# Polarshield_v2_2.net
KiCad netlist of a schematic drawn in EAGLE
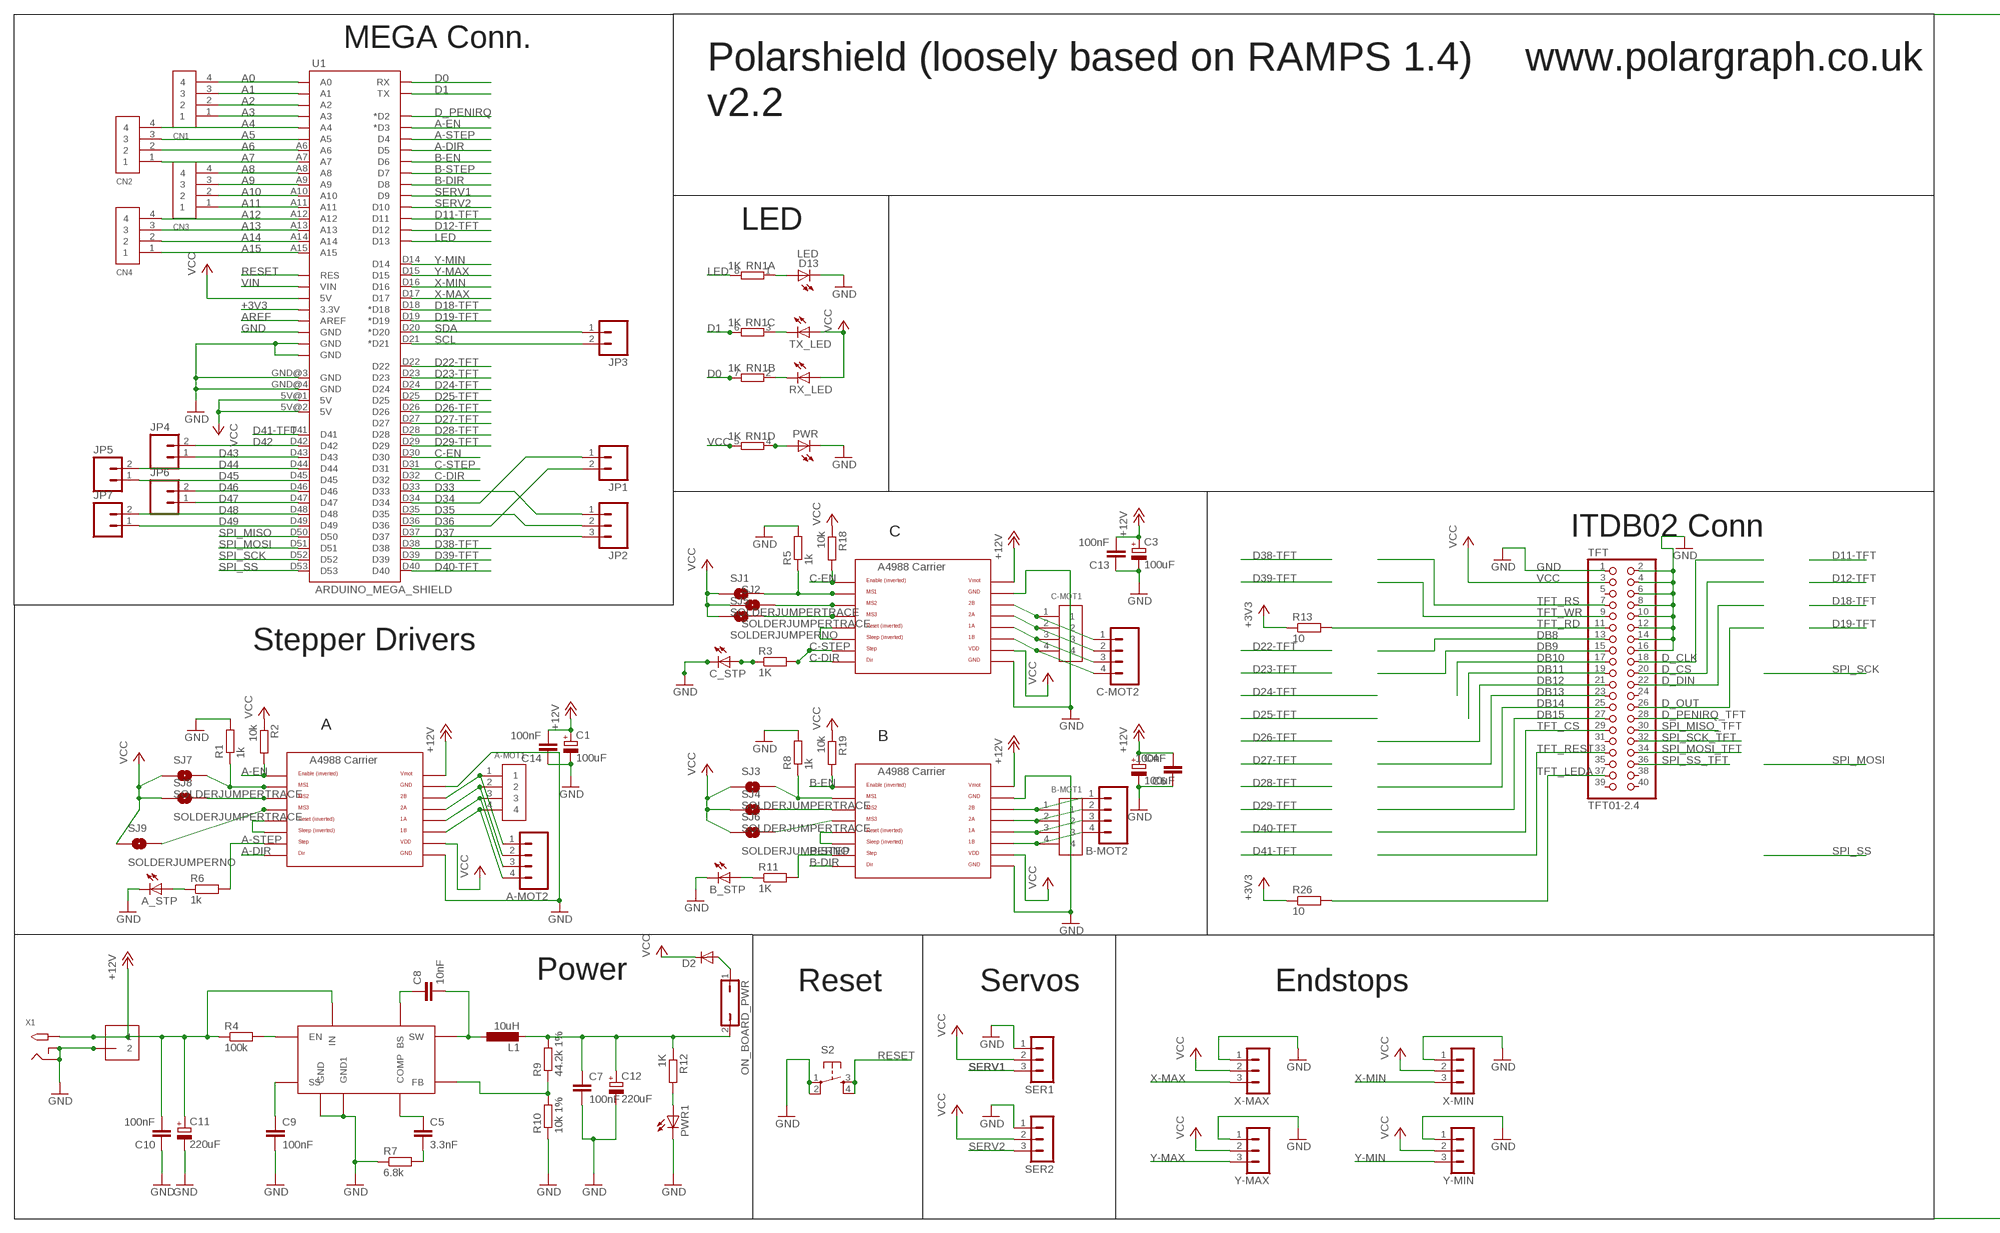
[diagram p0: schematic, sheet 1, part 1 of 2]
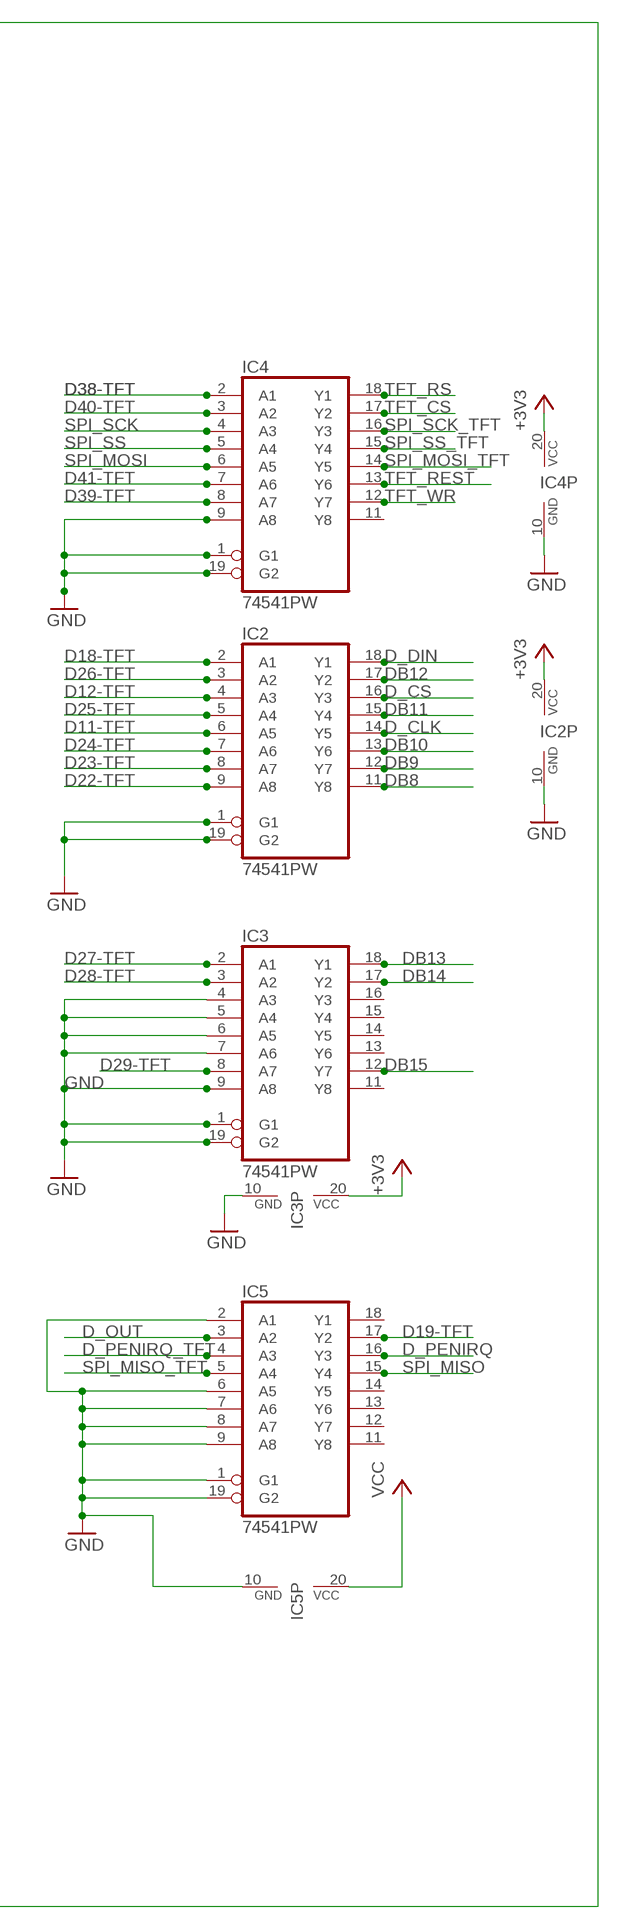
[diagram p1: schematic, sheet 1, part 2 of 2]

(export (version "E")
  (design (tool "Eeschema 10.0.6"))
  (components
    (comp (ref "A-MOT1")
      (value "1X4-BIG")
      (footprint "eagle-import:1X04-BIG")
      (libsource (lib "eagle-import") (part "adafruit_1X4-BIG"))
    )
    (comp (ref "A-MOT2")
      (value "M04SCREW")
      (footprint "eagle-import:SCREWTERMINAL-3.5MM-4")
      (libsource (lib "eagle-import") (part "M04SCREW"))
    )
    (comp (ref "A_STP")
      (value "LEDCHIP-LED0805")
      (footprint "eagle-import:CHIP-LED0805")
      (libsource (lib "eagle-import") (part "LEDCHIP-LED0805"))
    )
    (comp (ref "B-MOT1")
      (value "1X4-BIG")
      (footprint "eagle-import:1X04-BIG")
      (libsource (lib "eagle-import") (part "adafruit_1X4-BIG"))
    )
    (comp (ref "B-MOT2")
      (value "M04SCREW")
      (footprint "eagle-import:SCREWTERMINAL-3.5MM-4")
      (libsource (lib "eagle-import") (part "M04SCREW"))
    )
    (comp (ref "B_STP")
      (value "LEDCHIP-LED0805")
      (footprint "eagle-import:CHIP-LED0805")
      (libsource (lib "eagle-import") (part "LEDCHIP-LED0805"))
    )
    (comp (ref "C-MOT1")
      (value "1X4-BIG")
      (footprint "eagle-import:1X04-BIG")
      (libsource (lib "eagle-import") (part "adafruit_1X4-BIG"))
    )
    (comp (ref "C-MOT2")
      (value "M04SCREW")
      (footprint "eagle-import:SCREWTERMINAL-3.5MM-4")
      (libsource (lib "eagle-import") (part "M04SCREW"))
    )
    (comp (ref "C1")
      (value "100uF")
      (footprint "eagle-import:153CLV-0605")
      (libsource (lib "eagle-import") (part "CPOL-EU153CLV-0605"))
    )
    (comp (ref "C3")
      (value "100uF")
      (footprint "eagle-import:153CLV-0605")
      (libsource (lib "eagle-import") (part "CPOL-EU153CLV-0605"))
    )
    (comp (ref "C4")
      (value "100uF")
      (footprint "eagle-import:153CLV-0605")
      (libsource (lib "eagle-import") (part "CPOL-EU153CLV-0605"))
    )
    (comp (ref "C5")
      (value "3.3nF")
      (footprint "eagle-import:C0805K")
      (libsource (lib "eagle-import") (part "C-EUC0805K"))
    )
    (comp (ref "C6")
      (value "100nF")
      (footprint "eagle-import:C0805")
      (libsource (lib "eagle-import") (part "C-EUC0805"))
    )
    (comp (ref "C7")
      (value "100nF")
      (footprint "eagle-import:C0805K")
      (libsource (lib "eagle-import") (part "C-EUC0805K"))
    )
    (comp (ref "C8")
      (value "10nF")
      (footprint "eagle-import:C0805K")
      (libsource (lib "eagle-import") (part "C-EUC0805K"))
    )
    (comp (ref "C9")
      (value "100nF")
      (footprint "eagle-import:C0805K")
      (libsource (lib "eagle-import") (part "C-EUC0805K"))
    )
    (comp (ref "C10")
      (value "100nF")
      (footprint "eagle-import:C0805K")
      (libsource (lib "eagle-import") (part "C-EUC0805K"))
    )
    (comp (ref "C11")
      (value "220uF")
      (footprint "eagle-import:153CLV-0807")
      (libsource (lib "eagle-import") (part "resistor_CPOL-EU153CLV-0807"))
    )
    (comp (ref "C12")
      (value "220uF")
      (footprint "eagle-import:153CLV-0807")
      (libsource (lib "eagle-import") (part "resistor_CPOL-EU153CLV-0807"))
    )
    (comp (ref "C13")
      (value "100nF")
      (footprint "eagle-import:C0805")
      (libsource (lib "eagle-import") (part "C-EUC0805"))
    )
    (comp (ref "C14")
      (value "100nF")
      (footprint "eagle-import:C0805")
      (libsource (lib "eagle-import") (part "C-EUC0805"))
    )
    (comp (ref "CN1")
      (value "1X4-CLEANBIG")
      (footprint "eagle-import:1X04-CLEANBIG")
      (libsource (lib "eagle-import") (part "1X4-CLEANBIG"))
    )
    (comp (ref "CN2")
      (value "1X4-CLEANBIG")
      (footprint "eagle-import:1X04-CLEANBIG")
      (libsource (lib "eagle-import") (part "1X4-CLEANBIG"))
    )
    (comp (ref "CN3")
      (value "1X4-CLEANBIG")
      (footprint "eagle-import:1X04-CLEANBIG")
      (libsource (lib "eagle-import") (part "1X4-CLEANBIG"))
    )
    (comp (ref "CN4")
      (value "1X4-CLEANBIG")
      (footprint "eagle-import:1X04-CLEANBIG")
      (libsource (lib "eagle-import") (part "1X4-CLEANBIG"))
    )
    (comp (ref "C_STP")
      (value "LEDCHIP-LED0805")
      (footprint "eagle-import:CHIP-LED0805")
      (libsource (lib "eagle-import") (part "LEDCHIP-LED0805"))
    )
    (comp (ref "D2")
      (value "DIODE-DO214BA")
      (footprint "eagle-import:DO214BA")
      (libsource (lib "eagle-import") (part "DIODE-DO214BA"))
    )
    (comp (ref "D13")
      (value "LED")
      (footprint "eagle-import:CHIP-LED0805")
      (libsource (lib "eagle-import") (part "LEDCHIP-LED0805"))
    )
    (comp (ref "IC1")
      (value "MP2307")
      (footprint "eagle-import:SOIC8")
      (libsource (lib "eagle-import") (part "MP2307"))
    )
    (comp (ref "IC2")
      (value "74541PW")
      (footprint "eagle-import:TSSOP20")
      (libsource (lib "eagle-import") (part "74541PW"))
    )
    (comp (ref "IC3")
      (value "74541PW")
      (footprint "eagle-import:TSSOP20")
      (libsource (lib "eagle-import") (part "74541PW"))
    )
    (comp (ref "IC4")
      (value "74541PW")
      (footprint "eagle-import:TSSOP20")
      (libsource (lib "eagle-import") (part "74541PW"))
    )
    (comp (ref "IC5")
      (value "74541PW")
      (footprint "eagle-import:TSSOP20")
      (libsource (lib "eagle-import") (part "74541PW"))
    )
    (comp (ref "J1")
      (value "1X2-3.5MM")
      (footprint "eagle-import:1X2-3.5MM")
      (libsource (lib "eagle-import") (part "1X2-3.5MM"))
    )
    (comp (ref "JP1")
      (value "M02POGO_PIN_HOLES_ONLY")
      (footprint "eagle-import:1X02_PP_HOLES_ONLY")
      (libsource (lib "eagle-import") (part "M02POGO_PIN_HOLES_ONLY"))
    )
    (comp (ref "JP2")
      (value "M03POGO_PIN_HOLES_ONLY")
      (footprint "eagle-import:1X03_PP_HOLES_ONLY")
      (libsource (lib "eagle-import") (part "M03POGO_PIN_HOLES_ONLY"))
    )
    (comp (ref "JP3")
      (value "M02POGO_PIN_HOLES_ONLY")
      (footprint "eagle-import:1X02_PP_HOLES_ONLY")
      (libsource (lib "eagle-import") (part "M02POGO_PIN_HOLES_ONLY"))
    )
    (comp (ref "JP4")
      (value "M02POGO_PIN_HOLES_ONLY")
      (footprint "eagle-import:1X02_PP_HOLES_ONLY")
      (libsource (lib "eagle-import") (part "M02POGO_PIN_HOLES_ONLY"))
    )
    (comp (ref "JP5")
      (value "M02POGO_PIN_HOLES_ONLY")
      (footprint "eagle-import:1X02_PP_HOLES_ONLY")
      (libsource (lib "eagle-import") (part "M02POGO_PIN_HOLES_ONLY"))
    )
    (comp (ref "JP6")
      (value "M02POGO_PIN_HOLES_ONLY")
      (footprint "eagle-import:1X02_PP_HOLES_ONLY")
      (libsource (lib "eagle-import") (part "M02POGO_PIN_HOLES_ONLY"))
    )
    (comp (ref "JP7")
      (value "M02POGO_PIN_HOLES_ONLY")
      (footprint "eagle-import:1X02_PP_HOLES_ONLY")
      (libsource (lib "eagle-import") (part "M02POGO_PIN_HOLES_ONLY"))
    )
    (comp (ref "L1")
      (value "10uH")
      (footprint "eagle-import:PIS2816")
      (libsource (lib "eagle-import") (part "L-EUPIS2816"))
    )
    (comp (ref "ON_BOARD_PWR")
      (value "JP1Q")
      (footprint "eagle-import:JP1")
      (libsource (lib "eagle-import") (part "JP1Q"))
    )
    (comp (ref "PWR")
      (value "LEDCHIP-LED0805")
      (footprint "eagle-import:CHIP-LED0805")
      (libsource (lib "eagle-import") (part "LEDCHIP-LED0805"))
    )
    (comp (ref "PWR1")
      (value "LEDCHIP-LED0805")
      (footprint "eagle-import:CHIP-LED0805")
      (libsource (lib "eagle-import") (part "LEDCHIP-LED0805"))
    )
    (comp (ref "R1")
      (value "1k")
      (footprint "eagle-import:R0805")
      (libsource (lib "eagle-import") (part "R-EU_R0805"))
    )
    (comp (ref "R2")
      (value "10k")
      (footprint "eagle-import:R0805")
      (libsource (lib "eagle-import") (part "R-EU_R0805"))
    )
    (comp (ref "R3")
      (value "1K")
      (footprint "eagle-import:R0805")
      (libsource (lib "eagle-import") (part "R-EU_R0805"))
    )
    (comp (ref "R4")
      (value "100k")
      (footprint "eagle-import:R0805")
      (libsource (lib "eagle-import") (part "resistor_R-EU_R0805"))
    )
    (comp (ref "R5")
      (value "1k")
      (footprint "eagle-import:R0805")
      (libsource (lib "eagle-import") (part "R-EU_R0805"))
    )
    (comp (ref "R6")
      (value "1k")
      (footprint "eagle-import:R0805")
      (libsource (lib "eagle-import") (part "R-EU_R0805"))
    )
    (comp (ref "R7")
      (value "6.8k")
      (footprint "eagle-import:R0805")
      (libsource (lib "eagle-import") (part "resistor_R-EU_R0805"))
    )
    (comp (ref "R8")
      (value "1k")
      (footprint "eagle-import:R0805")
      (libsource (lib "eagle-import") (part "R-EU_R0805"))
    )
    (comp (ref "R9")
      (value "44.2k 1%")
      (footprint "eagle-import:R0805")
      (libsource (lib "eagle-import") (part "resistor_R-EU_R0805"))
    )
    (comp (ref "R10")
      (value "10k 1%")
      (footprint "eagle-import:R0805")
      (libsource (lib "eagle-import") (part "resistor_R-EU_R0805"))
    )
    (comp (ref "R11")
      (value "1K")
      (footprint "eagle-import:R0805")
      (libsource (lib "eagle-import") (part "R-EU_R0805"))
    )
    (comp (ref "R12")
      (value "1K")
      (footprint "eagle-import:R0805")
      (libsource (lib "eagle-import") (part "R-EU_R0805"))
    )
    (comp (ref "R13")
      (value "10")
      (footprint "eagle-import:R0805")
      (libsource (lib "eagle-import") (part "resistor_R-EU_R0805"))
    )
    (comp (ref "R18")
      (value "10k")
      (footprint "eagle-import:R0805")
      (libsource (lib "eagle-import") (part "R-EU_R0805"))
    )
    (comp (ref "R19")
      (value "10k")
      (footprint "eagle-import:R0805")
      (libsource (lib "eagle-import") (part "R-EU_R0805"))
    )
    (comp (ref "R26")
      (value "10")
      (footprint "eagle-import:R0805")
      (libsource (lib "eagle-import") (part "resistor_R-EU_R0805"))
    )
    (comp (ref "RN1")
      (value "1K")
      (footprint "eagle-import:EXBS8V")
      (libsource (lib "eagle-import") (part "4R-NEXBS8V"))
    )
    (comp (ref "RX_LED")
      (value "LEDCHIP-LED0805")
      (footprint "eagle-import:CHIP-LED0805")
      (libsource (lib "eagle-import") (part "LEDCHIP-LED0805"))
    )
    (comp (ref "S2")
      (value "TAC_SWITCHPTH")
      (footprint "eagle-import:TACTILE-PTH")
      (libsource (lib "eagle-import") (part "TAC_SWITCHPTH"))
    )
    (comp (ref "SER1")
      (value "3PIN-HEADER")
      (footprint "eagle-import:3PIN-HEADER")
      (libsource (lib "eagle-import") (part "3PIN-HEADER"))
    )
    (comp (ref "SER2")
      (value "3PIN-HEADER")
      (footprint "eagle-import:3PIN-HEADER")
      (libsource (lib "eagle-import") (part "3PIN-HEADER"))
    )
    (comp (ref "SJ1")
      (value "SOLDERJUMPERTRACE")
      (footprint "eagle-import:SJ_2S-TRACE")
      (libsource (lib "eagle-import") (part "SOLDERJUMPERTRACE"))
    )
    (comp (ref "SJ2")
      (value "SOLDERJUMPERTRACE")
      (footprint "eagle-import:SJ_2S-TRACE")
      (libsource (lib "eagle-import") (part "SOLDERJUMPERTRACE"))
    )
    (comp (ref "SJ3")
      (value "SOLDERJUMPERTRACE")
      (footprint "eagle-import:SJ_2S-TRACE")
      (libsource (lib "eagle-import") (part "SOLDERJUMPERTRACE"))
    )
    (comp (ref "SJ4")
      (value "SOLDERJUMPERTRACE")
      (footprint "eagle-import:SJ_2S-TRACE")
      (libsource (lib "eagle-import") (part "SOLDERJUMPERTRACE"))
    )
    (comp (ref "SJ5")
      (value "SOLDERJUMPERNO")
      (footprint "eagle-import:SJ_2S-NO")
      (libsource (lib "eagle-import") (part "SOLDERJUMPERNO"))
    )
    (comp (ref "SJ6")
      (value "SOLDERJUMPERNO")
      (footprint "eagle-import:SJ_2S-NO")
      (libsource (lib "eagle-import") (part "SOLDERJUMPERNO"))
    )
    (comp (ref "SJ7")
      (value "SOLDERJUMPERTRACE")
      (footprint "eagle-import:SJ_2S-TRACE")
      (libsource (lib "eagle-import") (part "SOLDERJUMPERTRACE"))
    )
    (comp (ref "SJ8")
      (value "SOLDERJUMPERTRACE")
      (footprint "eagle-import:SJ_2S-TRACE")
      (libsource (lib "eagle-import") (part "SOLDERJUMPERTRACE"))
    )
    (comp (ref "SJ9")
      (value "SOLDERJUMPERNO")
      (footprint "eagle-import:SJ_2S-NO")
      (libsource (lib "eagle-import") (part "SOLDERJUMPERNO"))
    )
    (comp (ref "TFT")
      (value "TFT01-2.4")
      (footprint "eagle-import:TFT01-2.4")
      (libsource (lib "eagle-import") (part "TFT01-2.4"))
    )
    (comp (ref "TX_LED")
      (value "LEDCHIP-LED0805")
      (footprint "eagle-import:CHIP-LED0805")
      (libsource (lib "eagle-import") (part "LEDCHIP-LED0805"))
    )
    (comp (ref "U$1")
      (value "A4988BREAKOUT")
      (footprint "eagle-import:A4988BREAKOUT")
      (libsource (lib "eagle-import") (part "A4988BREAKOUT"))
    )
    (comp (ref "U$6")
      (value "A4988BREAKOUT")
      (footprint "eagle-import:A4988BREAKOUT")
      (libsource (lib "eagle-import") (part "A4988BREAKOUT"))
    )
    (comp (ref "U$7")
      (value "A4988BREAKOUT")
      (footprint "eagle-import:A4988BREAKOUT")
      (libsource (lib "eagle-import") (part "A4988BREAKOUT"))
    )
    (comp (ref "U1")
      (value "ARDUINO_MEGA_SHIELD")
      (footprint "eagle-import:ARDUINO_MEGA_SHIELD")
      (libsource (lib "eagle-import") (part "ARDUINO_MEGA_SHIELD"))
    )
    (comp (ref "X-MAX")
      (value "3PIN-HEADER")
      (footprint "eagle-import:3PIN-HEADER")
      (libsource (lib "eagle-import") (part "3PIN-HEADER"))
    )
    (comp (ref "X-MIN")
      (value "3PIN-HEADER")
      (footprint "eagle-import:3PIN-HEADER")
      (libsource (lib "eagle-import") (part "3PIN-HEADER"))
    )
    (comp (ref "X1")
      (value "2.1MMJACKTHM")
      (footprint "eagle-import:PJ-102A")
      (libsource (lib "eagle-import") (part "2.1MMJACKTHM"))
    )
    (comp (ref "Y-MAX")
      (value "3PIN-HEADER")
      (footprint "eagle-import:3PIN-HEADER")
      (libsource (lib "eagle-import") (part "3PIN-HEADER"))
    )
    (comp (ref "Y-MIN")
      (value "3PIN-HEADER")
      (footprint "eagle-import:3PIN-HEADER")
      (libsource (lib "eagle-import") (part "3PIN-HEADER"))
    )
  )
  (nets
    (net (code "1") (name "+3V3") (class "Default")
      (node (ref "IC2") (pin "20") (pinfunction "VCC_20") (pintype "power_in"))
      (node (ref "IC3") (pin "20") (pinfunction "VCC_20") (pintype "power_in"))
      (node (ref "IC4") (pin "20") (pinfunction "VCC_20") (pintype "power_in"))
      (node (ref "R13") (pin "1") (pinfunction "1_1") (pintype "passive"))
      (node (ref "R26") (pin "1") (pinfunction "1_1") (pintype "passive"))
      (node (ref "U1") (pin "3.3V") (pinfunction "3.3V_3.3V") (pintype "bidirectional"))
    )
    (net (code "2") (name "+12V") (class "Default")
      (node (ref "C1") (pin "+") (pinfunction "+_+") (pintype "passive"))
      (node (ref "C10") (pin "2") (pinfunction "2_2") (pintype "passive"))
      (node (ref "C11") (pin "+") (pinfunction "+_+") (pintype "passive"))
      (node (ref "C13") (pin "2") (pinfunction "2_2") (pintype "passive"))
      (node (ref "C14") (pin "2") (pinfunction "2_2") (pintype "passive"))
      (node (ref "C3") (pin "+") (pinfunction "+_+") (pintype "passive"))
      (node (ref "C4") (pin "+") (pinfunction "+_+") (pintype "passive"))
      (node (ref "C6") (pin "2") (pinfunction "2_2") (pintype "passive"))
      (node (ref "IC1") (pin "IN") (pinfunction "IN_IN") (pintype "bidirectional"))
      (node (ref "J1") (pin "1") (pinfunction "1_1") (pintype "passive"))
      (node (ref "R4") (pin "1") (pinfunction "1_1") (pintype "passive"))
      (node (ref "U$1") (pin "VMOT") (pinfunction "VMOT_VMOT") (pintype "power_in"))
      (node (ref "U$6") (pin "VMOT") (pinfunction "VMOT_VMOT") (pintype "power_in"))
      (node (ref "U$7") (pin "VMOT") (pinfunction "VMOT_VMOT") (pintype "power_in"))
      (node (ref "X1") (pin "TIP") (pinfunction "TIP_TIP") (pintype "bidirectional"))
    )
    (net (code "3") (name "/A-DIR") (class "Default")
      (node (ref "U$1") (pin "DIR") (pinfunction "DIR_DIR") (pintype "input"))
      (node (ref "U1") (pin "D5") (pinfunction "D5_D5") (pintype "bidirectional"))
    )
    (net (code "4") (name "/A-EN") (class "Default")
      (node (ref "R2") (pin "2") (pinfunction "2_2") (pintype "passive"))
      (node (ref "U$1") (pin "EN") (pinfunction "EN_EN") (pintype "input"))
      (node (ref "U1") (pin "D3") (pinfunction "*D3_D3") (pintype "bidirectional"))
    )
    (net (code "5") (name "/A-STEP") (class "Default")
      (node (ref "R6") (pin "2") (pinfunction "2_2") (pintype "passive"))
      (node (ref "U$1") (pin "STEP") (pinfunction "STEP_STEP") (pintype "input"))
      (node (ref "U1") (pin "D4") (pinfunction "D4_D4") (pintype "bidirectional"))
    )
    (net (code "6") (name "/A0") (class "Default")
      (node (ref "CN1") (pin "4") (pinfunction "4_4") (pintype "bidirectional"))
      (node (ref "U1") (pin "A0") (pinfunction "A0_A0") (pintype "bidirectional"))
    )
    (net (code "7") (name "/A1") (class "Default")
      (node (ref "CN1") (pin "3") (pinfunction "3_3") (pintype "bidirectional"))
      (node (ref "U1") (pin "A1") (pinfunction "A1_A1") (pintype "bidirectional"))
    )
    (net (code "8") (name "/A2") (class "Default")
      (node (ref "CN1") (pin "2") (pinfunction "2_2") (pintype "bidirectional"))
      (node (ref "U1") (pin "A2") (pinfunction "A2_A2") (pintype "bidirectional"))
    )
    (net (code "9") (name "/A3") (class "Default")
      (node (ref "CN1") (pin "1") (pinfunction "1_1") (pintype "bidirectional"))
      (node (ref "U1") (pin "A3") (pinfunction "A3_A3") (pintype "bidirectional"))
    )
    (net (code "10") (name "/A4") (class "Default")
      (node (ref "CN2") (pin "4") (pinfunction "4_4") (pintype "bidirectional"))
      (node (ref "U1") (pin "A4") (pinfunction "A4_A4") (pintype "bidirectional"))
    )
    (net (code "11") (name "/A5") (class "Default")
      (node (ref "CN2") (pin "3") (pinfunction "3_3") (pintype "bidirectional"))
      (node (ref "U1") (pin "A5") (pinfunction "A5_A5") (pintype "bidirectional"))
    )
    (net (code "12") (name "/A6") (class "Default")
      (node (ref "CN2") (pin "2") (pinfunction "2_2") (pintype "bidirectional"))
      (node (ref "U1") (pin "A6") (pinfunction "A6_A6") (pintype "bidirectional"))
    )
    (net (code "13") (name "/A7") (class "Default")
      (node (ref "CN2") (pin "1") (pinfunction "1_1") (pintype "bidirectional"))
      (node (ref "U1") (pin "A7") (pinfunction "A7_A7") (pintype "bidirectional"))
    )
    (net (code "14") (name "/A8") (class "Default")
      (node (ref "CN3") (pin "4") (pinfunction "4_4") (pintype "bidirectional"))
      (node (ref "U1") (pin "A8") (pinfunction "A8_A8") (pintype "bidirectional"))
    )
    (net (code "15") (name "/A9") (class "Default")
      (node (ref "CN3") (pin "3") (pinfunction "3_3") (pintype "bidirectional"))
      (node (ref "U1") (pin "A9") (pinfunction "A9_A9") (pintype "bidirectional"))
    )
    (net (code "16") (name "/A10") (class "Default")
      (node (ref "CN3") (pin "2") (pinfunction "2_2") (pintype "bidirectional"))
      (node (ref "U1") (pin "A10") (pinfunction "A10_A10") (pintype "bidirectional"))
    )
    (net (code "17") (name "/A11") (class "Default")
      (node (ref "CN3") (pin "1") (pinfunction "1_1") (pintype "bidirectional"))
      (node (ref "U1") (pin "A11") (pinfunction "A11_A11") (pintype "bidirectional"))
    )
    (net (code "18") (name "/A12") (class "Default")
      (node (ref "CN4") (pin "4") (pinfunction "4_4") (pintype "bidirectional"))
      (node (ref "U1") (pin "A12") (pinfunction "A12_A12") (pintype "bidirectional"))
    )
    (net (code "19") (name "/A13") (class "Default")
      (node (ref "CN4") (pin "3") (pinfunction "3_3") (pintype "bidirectional"))
      (node (ref "U1") (pin "A13") (pinfunction "A13_A13") (pintype "bidirectional"))
    )
    (net (code "20") (name "/A14") (class "Default")
      (node (ref "CN4") (pin "2") (pinfunction "2_2") (pintype "bidirectional"))
      (node (ref "U1") (pin "A14") (pinfunction "A14_A14") (pintype "bidirectional"))
    )
    (net (code "21") (name "/A15") (class "Default")
      (node (ref "CN4") (pin "1") (pinfunction "1_1") (pintype "bidirectional"))
      (node (ref "U1") (pin "A15") (pinfunction "A15_A15") (pintype "bidirectional"))
    )
    (net (code "22") (name "/AREF") (class "Default")
      (node (ref "U1") (pin "AREF") (pinfunction "AREF_AREF") (pintype "bidirectional"))
    )
    (net (code "23") (name "/B-DIR") (class "Default")
      (node (ref "U$7") (pin "DIR") (pinfunction "DIR_DIR") (pintype "input"))
      (node (ref "U1") (pin "D8") (pinfunction "D8_D8") (pintype "bidirectional"))
    )
    (net (code "24") (name "/B-EN") (class "Default")
      (node (ref "R19") (pin "2") (pinfunction "2_2") (pintype "passive"))
      (node (ref "U$7") (pin "EN") (pinfunction "EN_EN") (pintype "input"))
      (node (ref "U1") (pin "D6") (pinfunction "D6_D6") (pintype "bidirectional"))
    )
    (net (code "25") (name "/B-STEP") (class "Default")
      (node (ref "R11") (pin "2") (pinfunction "2_2") (pintype "passive"))
      (node (ref "U$7") (pin "STEP") (pinfunction "STEP_STEP") (pintype "input"))
      (node (ref "U1") (pin "D7") (pinfunction "D7_D7") (pintype "bidirectional"))
    )
    (net (code "26") (name "/C-DIR") (class "Default")
      (node (ref "U$6") (pin "DIR") (pinfunction "DIR_DIR") (pintype "input"))
      (node (ref "U1") (pin "D32") (pinfunction "D32_D32") (pintype "bidirectional"))
    )
    (net (code "27") (name "/C-EN") (class "Default")
      (node (ref "R18") (pin "2") (pinfunction "2_2") (pintype "passive"))
      (node (ref "U$6") (pin "EN") (pinfunction "EN_EN") (pintype "input"))
      (node (ref "U1") (pin "D30") (pinfunction "D30_D30") (pintype "bidirectional"))
    )
    (net (code "28") (name "/C-STEP") (class "Default")
      (node (ref "R3") (pin "2") (pinfunction "2_2") (pintype "passive"))
      (node (ref "U$6") (pin "STEP") (pinfunction "STEP_STEP") (pintype "input"))
      (node (ref "U1") (pin "D31") (pinfunction "D31_D31") (pintype "bidirectional"))
    )
    (net (code "29") (name "/D0") (class "Default")
      (node (ref "RN1") (pin "7") (pinfunction "2_7") (pintype "passive"))
      (node (ref "U1") (pin "RX") (pinfunction "RX_RX") (pintype "bidirectional"))
    )
    (net (code "30") (name "/D1") (class "Default")
      (node (ref "RN1") (pin "6") (pinfunction "2_6") (pintype "passive"))
      (node (ref "U1") (pin "TX") (pinfunction "TX_TX") (pintype "bidirectional"))
    )
    (net (code "31") (name "/D11-TFT") (class "Default")
      (node (ref "IC2") (pin "6") (pinfunction "A5_6") (pintype "input"))
      (node (ref "U1") (pin "D11") (pinfunction "D11_D11") (pintype "bidirectional"))
    )
    (net (code "32") (name "/D12-TFT") (class "Default")
      (node (ref "IC2") (pin "4") (pinfunction "A3_4") (pintype "input"))
      (node (ref "U1") (pin "D12") (pinfunction "D12_D12") (pintype "bidirectional"))
    )
    (net (code "33") (name "/D18-TFT") (class "Default")
      (node (ref "IC2") (pin "2") (pinfunction "A1_2") (pintype "input"))
      (node (ref "U1") (pin "D18") (pinfunction "*D18_D18") (pintype "bidirectional"))
    )
    (net (code "34") (name "/D19-TFT") (class "Default")
      (node (ref "IC5") (pin "17") (pinfunction "Y2_17") (pintype "tri_state"))
      (node (ref "U1") (pin "D19") (pinfunction "*D19_D19") (pintype "bidirectional"))
    )
    (net (code "35") (name "/D22-TFT") (class "Default")
      (node (ref "IC2") (pin "9") (pinfunction "A8_9") (pintype "input"))
      (node (ref "U1") (pin "D22") (pinfunction "D22_D22") (pintype "bidirectional"))
    )
    (net (code "36") (name "/D23-TFT") (class "Default")
      (node (ref "IC2") (pin "8") (pinfunction "A7_8") (pintype "input"))
      (node (ref "U1") (pin "D23") (pinfunction "D23_D23") (pintype "bidirectional"))
    )
    (net (code "37") (name "/D24-TFT") (class "Default")
      (node (ref "IC2") (pin "7") (pinfunction "A6_7") (pintype "input"))
      (node (ref "U1") (pin "D24") (pinfunction "D24_D24") (pintype "bidirectional"))
    )
    (net (code "38") (name "/D25-TFT") (class "Default")
      (node (ref "IC2") (pin "5") (pinfunction "A4_5") (pintype "input"))
      (node (ref "U1") (pin "D25") (pinfunction "D25_D25") (pintype "bidirectional"))
    )
    (net (code "39") (name "/D26-TFT") (class "Default")
      (node (ref "IC2") (pin "3") (pinfunction "A2_3") (pintype "input"))
      (node (ref "U1") (pin "D26") (pinfunction "D26_D26") (pintype "bidirectional"))
    )
    (net (code "40") (name "/D27-TFT") (class "Default")
      (node (ref "IC3") (pin "2") (pinfunction "A1_2") (pintype "input"))
      (node (ref "U1") (pin "D27") (pinfunction "D27_D27") (pintype "bidirectional"))
    )
    (net (code "41") (name "/D28-TFT") (class "Default")
      (node (ref "IC3") (pin "3") (pinfunction "A2_3") (pintype "input"))
      (node (ref "U1") (pin "D28") (pinfunction "D28_D28") (pintype "bidirectional"))
    )
    (net (code "42") (name "/D29-TFT") (class "Default")
      (node (ref "IC3") (pin "8") (pinfunction "A7_8") (pintype "input"))
      (node (ref "U1") (pin "D29") (pinfunction "D29_D29") (pintype "bidirectional"))
    )
    (net (code "43") (name "/D33") (class "Default")
      (node (ref "JP2") (pin "1") (pinfunction "1_1") (pintype "passive"))
      (node (ref "U1") (pin "D33") (pinfunction "D33_D33") (pintype "bidirectional"))
    )
    (net (code "44") (name "/D34") (class "Default")
      (node (ref "JP1") (pin "1") (pinfunction "1_1") (pintype "passive"))
      (node (ref "U1") (pin "D34") (pinfunction "D34_D34") (pintype "bidirectional"))
    )
    (net (code "45") (name "/D35") (class "Default")
      (node (ref "JP2") (pin "2") (pinfunction "2_2") (pintype "passive"))
      (node (ref "U1") (pin "D35") (pinfunction "D35_D35") (pintype "bidirectional"))
    )
    (net (code "46") (name "/D36") (class "Default")
      (node (ref "JP1") (pin "2") (pinfunction "2_2") (pintype "passive"))
      (node (ref "U1") (pin "D36") (pinfunction "D36_D36") (pintype "bidirectional"))
    )
    (net (code "47") (name "/D37") (class "Default")
      (node (ref "JP2") (pin "3") (pinfunction "3_3") (pintype "passive"))
      (node (ref "U1") (pin "D37") (pinfunction "D37_D37") (pintype "bidirectional"))
    )
    (net (code "48") (name "/D38-TFT") (class "Default")
      (node (ref "IC4") (pin "2") (pinfunction "A1_2") (pintype "input"))
      (node (ref "U1") (pin "D38") (pinfunction "D38_D38") (pintype "bidirectional"))
    )
    (net (code "49") (name "/D39-TFT") (class "Default")
      (node (ref "IC4") (pin "8") (pinfunction "A7_8") (pintype "input"))
      (node (ref "U1") (pin "D39") (pinfunction "D39_D39") (pintype "bidirectional"))
    )
    (net (code "50") (name "/D40-TFT") (class "Default")
      (node (ref "IC4") (pin "3") (pinfunction "A2_3") (pintype "input"))
      (node (ref "U1") (pin "D40") (pinfunction "D40_D40") (pintype "bidirectional"))
    )
    (net (code "51") (name "/D41-TFT") (class "Default")
      (node (ref "IC4") (pin "7") (pinfunction "A6_7") (pintype "input"))
      (node (ref "U1") (pin "D41") (pinfunction "D41_D41") (pintype "bidirectional"))
    )
    (net (code "52") (name "/D42") (class "Default")
      (node (ref "JP4") (pin "2") (pinfunction "2_2") (pintype "passive"))
      (node (ref "U1") (pin "D42") (pinfunction "D42_D42") (pintype "bidirectional"))
    )
    (net (code "53") (name "/D43") (class "Default")
      (node (ref "JP4") (pin "1") (pinfunction "1_1") (pintype "passive"))
      (node (ref "U1") (pin "D43") (pinfunction "D43_D43") (pintype "bidirectional"))
    )
    (net (code "54") (name "/D44") (class "Default")
      (node (ref "JP5") (pin "2") (pinfunction "2_2") (pintype "passive"))
      (node (ref "U1") (pin "D44") (pinfunction "D44_D44") (pintype "bidirectional"))
    )
    (net (code "55") (name "/D45") (class "Default")
      (node (ref "JP5") (pin "1") (pinfunction "1_1") (pintype "passive"))
      (node (ref "U1") (pin "D45") (pinfunction "D45_D45") (pintype "bidirectional"))
    )
    (net (code "56") (name "/D46") (class "Default")
      (node (ref "JP6") (pin "2") (pinfunction "2_2") (pintype "passive"))
      (node (ref "U1") (pin "D46") (pinfunction "D46_D46") (pintype "bidirectional"))
    )
    (net (code "57") (name "/D47") (class "Default")
      (node (ref "JP6") (pin "1") (pinfunction "1_1") (pintype "passive"))
      (node (ref "U1") (pin "D47") (pinfunction "D47_D47") (pintype "bidirectional"))
    )
    (net (code "58") (name "/D48") (class "Default")
      (node (ref "JP7") (pin "2") (pinfunction "2_2") (pintype "passive"))
      (node (ref "U1") (pin "D48") (pinfunction "D48_D48") (pintype "bidirectional"))
    )
    (net (code "59") (name "/D49") (class "Default")
      (node (ref "JP7") (pin "1") (pinfunction "1_1") (pintype "passive"))
      (node (ref "U1") (pin "D49") (pinfunction "D49_D49") (pintype "bidirectional"))
    )
    (net (code "60") (name "/DB8") (class "Default")
      (node (ref "IC2") (pin "11") (pinfunction "Y8_11") (pintype "tri_state"))
      (node (ref "TFT") (pin "13") (pinfunction "13_13") (pintype "passive"))
    )
    (net (code "61") (name "/DB9") (class "Default")
      (node (ref "IC2") (pin "12") (pinfunction "Y7_12") (pintype "tri_state"))
      (node (ref "TFT") (pin "15") (pinfunction "15_15") (pintype "passive"))
    )
    (net (code "62") (name "/DB10") (class "Default")
      (node (ref "IC2") (pin "13") (pinfunction "Y6_13") (pintype "tri_state"))
      (node (ref "TFT") (pin "17") (pinfunction "17_17") (pintype "passive"))
    )
    (net (code "63") (name "/DB11") (class "Default")
      (node (ref "IC2") (pin "15") (pinfunction "Y4_15") (pintype "tri_state"))
      (node (ref "TFT") (pin "19") (pinfunction "19_19") (pintype "passive"))
    )
    (net (code "64") (name "/DB12") (class "Default")
      (node (ref "IC2") (pin "17") (pinfunction "Y2_17") (pintype "tri_state"))
      (node (ref "TFT") (pin "21") (pinfunction "21_21") (pintype "passive"))
    )
    (net (code "65") (name "/DB13") (class "Default")
      (node (ref "IC3") (pin "18") (pinfunction "Y1_18") (pintype "tri_state"))
      (node (ref "TFT") (pin "23") (pinfunction "23_23") (pintype "passive"))
    )
    (net (code "66") (name "/DB14") (class "Default")
      (node (ref "IC3") (pin "17") (pinfunction "Y2_17") (pintype "tri_state"))
      (node (ref "TFT") (pin "25") (pinfunction "25_25") (pintype "passive"))
    )
    (net (code "67") (name "/DB15") (class "Default")
      (node (ref "IC3") (pin "12") (pinfunction "Y7_12") (pintype "tri_state"))
      (node (ref "TFT") (pin "27") (pinfunction "27_27") (pintype "passive"))
    )
    (net (code "68") (name "/D_CLK") (class "Default")
      (node (ref "IC2") (pin "14") (pinfunction "Y5_14") (pintype "tri_state"))
      (node (ref "TFT") (pin "18") (pinfunction "18_18") (pintype "passive"))
    )
    (net (code "69") (name "/D_CS") (class "Default")
      (node (ref "IC2") (pin "16") (pinfunction "Y3_16") (pintype "tri_state"))
      (node (ref "TFT") (pin "20") (pinfunction "20_20") (pintype "passive"))
    )
    (net (code "70") (name "/D_DIN") (class "Default")
      (node (ref "IC2") (pin "18") (pinfunction "Y1_18") (pintype "tri_state"))
      (node (ref "TFT") (pin "22") (pinfunction "22_22") (pintype "passive"))
    )
    (net (code "71") (name "/D_OUT") (class "Default")
      (node (ref "IC5") (pin "3") (pinfunction "A2_3") (pintype "input"))
      (node (ref "TFT") (pin "26") (pinfunction "26_26") (pintype "passive"))
    )
    (net (code "72") (name "/D_PENIRQ") (class "Default")
      (node (ref "IC5") (pin "16") (pinfunction "Y3_16") (pintype "tri_state"))
      (node (ref "U1") (pin "D2") (pinfunction "*D2_D2") (pintype "bidirectional"))
    )
    (net (code "73") (name "/D_PENIRQ_TFT") (class "Default")
      (node (ref "IC5") (pin "4") (pinfunction "A3_4") (pintype "input"))
      (node (ref "TFT") (pin "28") (pinfunction "28_28") (pintype "passive"))
    )
    (net (code "74") (name "/LED") (class "Default")
      (node (ref "RN1") (pin "8") (pinfunction "2_8") (pintype "passive"))
      (node (ref "U1") (pin "D13") (pinfunction "D13_D13") (pintype "bidirectional"))
    )
    (net (code "75") (name "/RESET") (class "Default")
      (node (ref "S2") (pin "3") (pinfunction "3_3") (pintype "passive"))
      (node (ref "S2") (pin "4") (pinfunction "4_4") (pintype "passive"))
      (node (ref "U1") (pin "RES") (pinfunction "RES_RES") (pintype "bidirectional"))
    )
    (net (code "76") (name "/SCL") (class "Default")
      (node (ref "JP3") (pin "2") (pinfunction "2_2") (pintype "passive"))
      (node (ref "U1") (pin "D21") (pinfunction "*D21_D21") (pintype "bidirectional"))
    )
    (net (code "77") (name "/SDA") (class "Default")
      (node (ref "JP3") (pin "1") (pinfunction "1_1") (pintype "passive"))
      (node (ref "U1") (pin "D20") (pinfunction "*D20_D20") (pintype "bidirectional"))
    )
    (net (code "78") (name "/SERV1") (class "Default")
      (node (ref "SER1") (pin "3") (pinfunction "3_3") (pintype "passive"))
      (node (ref "U1") (pin "D9") (pinfunction "D9_D9") (pintype "bidirectional"))
    )
    (net (code "79") (name "/SERV2") (class "Default")
      (node (ref "SER2") (pin "3") (pinfunction "3_3") (pintype "passive"))
      (node (ref "U1") (pin "D10") (pinfunction "D10_D10") (pintype "bidirectional"))
    )
    (net (code "80") (name "/SPI_MISO") (class "Default")
      (node (ref "IC5") (pin "15") (pinfunction "Y4_15") (pintype "tri_state"))
      (node (ref "U1") (pin "D50") (pinfunction "D50_D50") (pintype "bidirectional"))
    )
    (net (code "81") (name "/SPI_MISO_TFT") (class "Default")
      (node (ref "IC5") (pin "5") (pinfunction "A4_5") (pintype "input"))
      (node (ref "TFT") (pin "30") (pinfunction "30_30") (pintype "passive"))
    )
    (net (code "82") (name "/SPI_MOSI") (class "Default")
      (node (ref "IC4") (pin "6") (pinfunction "A5_6") (pintype "input"))
      (node (ref "U1") (pin "D51") (pinfunction "D51_D51") (pintype "bidirectional"))
    )
    (net (code "83") (name "/SPI_MOSI_TFT") (class "Default")
      (node (ref "IC4") (pin "14") (pinfunction "Y5_14") (pintype "tri_state"))
      (node (ref "TFT") (pin "34") (pinfunction "34_34") (pintype "passive"))
    )
    (net (code "84") (name "/SPI_SCK") (class "Default")
      (node (ref "IC4") (pin "4") (pinfunction "A3_4") (pintype "input"))
      (node (ref "U1") (pin "D52") (pinfunction "D52_D52") (pintype "bidirectional"))
    )
    (net (code "85") (name "/SPI_SCK_TFT") (class "Default")
      (node (ref "IC4") (pin "16") (pinfunction "Y3_16") (pintype "tri_state"))
      (node (ref "TFT") (pin "32") (pinfunction "32_32") (pintype "passive"))
    )
    (net (code "86") (name "/SPI_SS") (class "Default")
      (node (ref "IC4") (pin "5") (pinfunction "A4_5") (pintype "input"))
      (node (ref "U1") (pin "D53") (pinfunction "D53_D53") (pintype "bidirectional"))
    )
    (net (code "87") (name "/SPI_SS_TFT") (class "Default")
      (node (ref "IC4") (pin "15") (pinfunction "Y4_15") (pintype "tri_state"))
      (node (ref "TFT") (pin "36") (pinfunction "36_36") (pintype "passive"))
    )
    (net (code "88") (name "/TFT_CS") (class "Default")
      (node (ref "IC4") (pin "17") (pinfunction "Y2_17") (pintype "tri_state"))
      (node (ref "TFT") (pin "29") (pinfunction "29_29") (pintype "passive"))
    )
    (net (code "89") (name "/TFT_LEDA") (class "Default")
      (node (ref "R26") (pin "2") (pinfunction "2_2") (pintype "passive"))
      (node (ref "TFT") (pin "37") (pinfunction "37_37") (pintype "passive"))
    )
    (net (code "90") (name "/TFT_RD") (class "Default")
      (node (ref "R13") (pin "2") (pinfunction "2_2") (pintype "passive"))
      (node (ref "TFT") (pin "11") (pinfunction "11_11") (pintype "passive"))
    )
    (net (code "91") (name "/TFT_REST") (class "Default")
      (node (ref "IC4") (pin "13") (pinfunction "Y6_13") (pintype "tri_state"))
      (node (ref "TFT") (pin "33") (pinfunction "33_33") (pintype "passive"))
    )
    (net (code "92") (name "/TFT_RS") (class "Default")
      (node (ref "IC4") (pin "18") (pinfunction "Y1_18") (pintype "tri_state"))
      (node (ref "TFT") (pin "7") (pinfunction "7_7") (pintype "passive"))
    )
    (net (code "93") (name "/TFT_WR") (class "Default")
      (node (ref "IC4") (pin "12") (pinfunction "Y7_12") (pintype "tri_state"))
      (node (ref "TFT") (pin "9") (pinfunction "9_9") (pintype "passive"))
    )
    (net (code "94") (name "/VIN") (class "Default")
      (node (ref "U1") (pin "VIN") (pinfunction "VIN_VIN") (pintype "bidirectional"))
    )
    (net (code "95") (name "/X-MAX") (class "Default")
      (node (ref "U1") (pin "D17") (pinfunction "D17_D17") (pintype "bidirectional"))
      (node (ref "X-MAX") (pin "3") (pinfunction "3_3") (pintype "passive"))
    )
    (net (code "96") (name "/X-MIN") (class "Default")
      (node (ref "U1") (pin "D16") (pinfunction "D16_D16") (pintype "bidirectional"))
      (node (ref "X-MIN") (pin "3") (pinfunction "3_3") (pintype "passive"))
    )
    (net (code "97") (name "/Y-MAX") (class "Default")
      (node (ref "U1") (pin "D15") (pinfunction "D15_D15") (pintype "bidirectional"))
      (node (ref "Y-MAX") (pin "3") (pinfunction "3_3") (pintype "passive"))
    )
    (net (code "98") (name "/Y-MIN") (class "Default")
      (node (ref "U1") (pin "D14") (pinfunction "D14_D14") (pintype "bidirectional"))
      (node (ref "Y-MIN") (pin "3") (pinfunction "3_3") (pintype "passive"))
    )
    (net (code "99") (name "GND") (class "Default")
      (node (ref "A_STP") (pin "C") (pinfunction "C_C") (pintype "passive"))
      (node (ref "B_STP") (pin "C") (pinfunction "C_C") (pintype "passive"))
      (node (ref "C1") (pin "-") (pinfunction "-_-") (pintype "passive"))
      (node (ref "C10") (pin "1") (pinfunction "1_1") (pintype "passive"))
      (node (ref "C11") (pin "-") (pinfunction "-_-") (pintype "passive"))
      (node (ref "C12") (pin "-") (pinfunction "-_-") (pintype "passive"))
      (node (ref "C13") (pin "1") (pinfunction "1_1") (pintype "passive"))
      (node (ref "C14") (pin "1") (pinfunction "1_1") (pintype "passive"))
      (node (ref "C3") (pin "-") (pinfunction "-_-") (pintype "passive"))
      (node (ref "C4") (pin "-") (pinfunction "-_-") (pintype "passive"))
      (node (ref "C6") (pin "1") (pinfunction "1_1") (pintype "passive"))
      (node (ref "C7") (pin "2") (pinfunction "2_2") (pintype "passive"))
      (node (ref "C9") (pin "2") (pinfunction "2_2") (pintype "passive"))
      (node (ref "C_STP") (pin "C") (pinfunction "C_C") (pintype "passive"))
      (node (ref "D13") (pin "C") (pinfunction "C_C") (pintype "passive"))
      (node (ref "IC1") (pin "GND") (pinfunction "GND_GND") (pintype "bidirectional"))
      (node (ref "IC1") (pin "GND1") (pinfunction "GND1_GND1") (pintype "bidirectional"))
      (node (ref "IC2") (pin "1") (pinfunction "G1_1") (pintype "input"))
      (node (ref "IC2") (pin "10") (pinfunction "GND_10") (pintype "power_in"))
      (node (ref "IC2") (pin "19") (pinfunction "G2_19") (pintype "input"))
      (node (ref "IC3") (pin "1") (pinfunction "G1_1") (pintype "input"))
      (node (ref "IC3") (pin "10") (pinfunction "GND_10") (pintype "power_in"))
      (node (ref "IC3") (pin "19") (pinfunction "G2_19") (pintype "input"))
      (node (ref "IC3") (pin "4") (pinfunction "A3_4") (pintype "input"))
      (node (ref "IC3") (pin "5") (pinfunction "A4_5") (pintype "input"))
      (node (ref "IC3") (pin "6") (pinfunction "A5_6") (pintype "input"))
      (node (ref "IC3") (pin "7") (pinfunction "A6_7") (pintype "input"))
      (node (ref "IC3") (pin "9") (pinfunction "A8_9") (pintype "input"))
      (node (ref "IC4") (pin "1") (pinfunction "G1_1") (pintype "input"))
      (node (ref "IC4") (pin "10") (pinfunction "GND_10") (pintype "power_in"))
      (node (ref "IC4") (pin "19") (pinfunction "G2_19") (pintype "input"))
      (node (ref "IC4") (pin "9") (pinfunction "A8_9") (pintype "input"))
      (node (ref "IC5") (pin "1") (pinfunction "G1_1") (pintype "input"))
      (node (ref "IC5") (pin "10") (pinfunction "GND_10") (pintype "power_in"))
      (node (ref "IC5") (pin "19") (pinfunction "G2_19") (pintype "input"))
      (node (ref "IC5") (pin "2") (pinfunction "A1_2") (pintype "input"))
      (node (ref "IC5") (pin "6") (pinfunction "A5_6") (pintype "input"))
      (node (ref "IC5") (pin "7") (pinfunction "A6_7") (pintype "input"))
      (node (ref "IC5") (pin "8") (pinfunction "A7_8") (pintype "input"))
      (node (ref "IC5") (pin "9") (pinfunction "A8_9") (pintype "input"))
      (node (ref "J1") (pin "2") (pinfunction "2_2") (pintype "passive"))
      (node (ref "PWR") (pin "C") (pinfunction "C_C") (pintype "passive"))
      (node (ref "PWR1") (pin "C") (pinfunction "C_C") (pintype "passive"))
      (node (ref "R1") (pin "2") (pinfunction "2_2") (pintype "passive"))
      (node (ref "R10") (pin "1") (pinfunction "1_1") (pintype "passive"))
      (node (ref "R5") (pin "2") (pinfunction "2_2") (pintype "passive"))
      (node (ref "R7") (pin "1") (pinfunction "1_1") (pintype "passive"))
      (node (ref "R8") (pin "2") (pinfunction "2_2") (pintype "passive"))
      (node (ref "S2") (pin "1") (pinfunction "1_1") (pintype "passive"))
      (node (ref "S2") (pin "2") (pinfunction "2_2") (pintype "passive"))
      (node (ref "SER1") (pin "1") (pinfunction "1_1") (pintype "passive"))
      (node (ref "SER2") (pin "1") (pinfunction "1_1") (pintype "passive"))
      (node (ref "TFT") (pin "1") (pinfunction "1_1") (pintype "passive"))
      (node (ref "TFT") (pin "10") (pinfunction "10_10") (pintype "passive"))
      (node (ref "TFT") (pin "12") (pinfunction "12_12") (pintype "passive"))
      (node (ref "TFT") (pin "14") (pinfunction "14_14") (pintype "passive"))
      (node (ref "TFT") (pin "16") (pinfunction "16_16") (pintype "passive"))
      (node (ref "TFT") (pin "2") (pinfunction "2_2") (pintype "passive"))
      (node (ref "TFT") (pin "4") (pinfunction "4_4") (pintype "passive"))
      (node (ref "TFT") (pin "6") (pinfunction "6_6") (pintype "passive"))
      (node (ref "TFT") (pin "8") (pinfunction "8_8") (pintype "passive"))
      (node (ref "U$1") (pin "GND") (pinfunction "GND_GND") (pintype "power_in"))
      (node (ref "U$1") (pin "GND@0") (pinfunction "GND_GND@0") (pintype "power_in"))
      (node (ref "U$6") (pin "GND") (pinfunction "GND_GND") (pintype "power_in"))
      (node (ref "U$6") (pin "GND@0") (pinfunction "GND_GND@0") (pintype "power_in"))
      (node (ref "U$7") (pin "GND") (pinfunction "GND_GND") (pintype "power_in"))
      (node (ref "U$7") (pin "GND@0") (pinfunction "GND_GND@0") (pintype "power_in"))
      (node (ref "U1") (pin "GND@0") (pinfunction "GND_GND@0") (pintype "power_in"))
      (node (ref "U1") (pin "GND@1") (pinfunction "GND_GND@1") (pintype "power_in"))
      (node (ref "U1") (pin "GND@2") (pinfunction "GND_GND@2") (pintype "power_in"))
      (node (ref "U1") (pin "GND@3") (pinfunction "GND_GND@3") (pintype "power_in"))
      (node (ref "U1") (pin "GND@4") (pinfunction "GND_GND@4") (pintype "power_in"))
      (node (ref "X-MAX") (pin "1") (pinfunction "1_1") (pintype "passive"))
      (node (ref "X-MIN") (pin "1") (pinfunction "1_1") (pintype "passive"))
      (node (ref "X1") (pin "RING") (pinfunction "RING_RING") (pintype "bidirectional"))
      (node (ref "X1") (pin "RING_SW") (pinfunction "RING_SW_RING_SW") (pintype "bidirectional"))
      (node (ref "Y-MAX") (pin "1") (pinfunction "1_1") (pintype "passive"))
      (node (ref "Y-MIN") (pin "1") (pinfunction "1_1") (pintype "passive"))
    )
    (net (code "100") (name "Net-(A-MOT1-Pad1)") (class "Default")
      (node (ref "A-MOT1") (pin "1") (pinfunction "1_1") (pintype "bidirectional"))
      (node (ref "A-MOT2") (pin "1") (pinfunction "1_1") (pintype "passive"))
      (node (ref "U$1") (pin "2B") (pinfunction "2B_2B") (pintype "output"))
    )
    (net (code "101") (name "Net-(A-MOT1-Pad2)") (class "Default")
      (node (ref "A-MOT1") (pin "2") (pinfunction "2_2") (pintype "bidirectional"))
      (node (ref "A-MOT2") (pin "2") (pinfunction "2_2") (pintype "passive"))
      (node (ref "U$1") (pin "2A") (pinfunction "2A_2A") (pintype "output"))
    )
    (net (code "102") (name "Net-(A-MOT1-Pad3)") (class "Default")
      (node (ref "A-MOT1") (pin "3") (pinfunction "3_3") (pintype "bidirectional"))
      (node (ref "A-MOT2") (pin "3") (pinfunction "3_3") (pintype "passive"))
      (node (ref "U$1") (pin "1A") (pinfunction "1A_1A") (pintype "output"))
    )
    (net (code "103") (name "Net-(A-MOT1-Pad4)") (class "Default")
      (node (ref "A-MOT1") (pin "4") (pinfunction "4_4") (pintype "bidirectional"))
      (node (ref "A-MOT2") (pin "4") (pinfunction "4_4") (pintype "passive"))
      (node (ref "U$1") (pin "1B") (pinfunction "1B_1B") (pintype "output"))
    )
    (net (code "104") (name "Net-(A_STP-PadA)") (class "Default")
      (node (ref "A_STP") (pin "A") (pinfunction "A_A") (pintype "passive"))
      (node (ref "R6") (pin "1") (pinfunction "1_1") (pintype "passive"))
    )
    (net (code "105") (name "Net-(B-MOT1-Pad1)") (class "Default")
      (node (ref "B-MOT1") (pin "1") (pinfunction "1_1") (pintype "bidirectional"))
      (node (ref "B-MOT2") (pin "1") (pinfunction "1_1") (pintype "passive"))
      (node (ref "U$7") (pin "2B") (pinfunction "2B_2B") (pintype "output"))
    )
    (net (code "106") (name "Net-(B-MOT1-Pad2)") (class "Default")
      (node (ref "B-MOT1") (pin "2") (pinfunction "2_2") (pintype "bidirectional"))
      (node (ref "B-MOT2") (pin "2") (pinfunction "2_2") (pintype "passive"))
      (node (ref "U$7") (pin "2A") (pinfunction "2A_2A") (pintype "output"))
    )
    (net (code "107") (name "Net-(B-MOT1-Pad3)") (class "Default")
      (node (ref "B-MOT1") (pin "3") (pinfunction "3_3") (pintype "bidirectional"))
      (node (ref "B-MOT2") (pin "3") (pinfunction "3_3") (pintype "passive"))
      (node (ref "U$7") (pin "1A") (pinfunction "1A_1A") (pintype "output"))
    )
    (net (code "108") (name "Net-(B-MOT1-Pad4)") (class "Default")
      (node (ref "B-MOT1") (pin "4") (pinfunction "4_4") (pintype "bidirectional"))
      (node (ref "B-MOT2") (pin "4") (pinfunction "4_4") (pintype "passive"))
      (node (ref "U$7") (pin "1B") (pinfunction "1B_1B") (pintype "output"))
    )
    (net (code "109") (name "Net-(B_STP-PadA)") (class "Default")
      (node (ref "B_STP") (pin "A") (pinfunction "A_A") (pintype "passive"))
      (node (ref "R11") (pin "1") (pinfunction "1_1") (pintype "passive"))
    )
    (net (code "110") (name "Net-(C-MOT1-Pad1)") (class "Default")
      (node (ref "C-MOT1") (pin "1") (pinfunction "1_1") (pintype "bidirectional"))
      (node (ref "C-MOT2") (pin "1") (pinfunction "1_1") (pintype "passive"))
      (node (ref "U$6") (pin "2B") (pinfunction "2B_2B") (pintype "output"))
    )
    (net (code "111") (name "Net-(C-MOT1-Pad2)") (class "Default")
      (node (ref "C-MOT1") (pin "2") (pinfunction "2_2") (pintype "bidirectional"))
      (node (ref "C-MOT2") (pin "2") (pinfunction "2_2") (pintype "passive"))
      (node (ref "U$6") (pin "2A") (pinfunction "2A_2A") (pintype "output"))
    )
    (net (code "112") (name "Net-(C-MOT1-Pad3)") (class "Default")
      (node (ref "C-MOT1") (pin "3") (pinfunction "3_3") (pintype "bidirectional"))
      (node (ref "C-MOT2") (pin "3") (pinfunction "3_3") (pintype "passive"))
      (node (ref "U$6") (pin "1A") (pinfunction "1A_1A") (pintype "output"))
    )
    (net (code "113") (name "Net-(C-MOT1-Pad4)") (class "Default")
      (node (ref "C-MOT1") (pin "4") (pinfunction "4_4") (pintype "bidirectional"))
      (node (ref "C-MOT2") (pin "4") (pinfunction "4_4") (pintype "passive"))
      (node (ref "U$6") (pin "1B") (pinfunction "1B_1B") (pintype "output"))
    )
    (net (code "114") (name "Net-(C5-Pad1)") (class "Default")
      (node (ref "C5") (pin "1") (pinfunction "1_1") (pintype "passive"))
      (node (ref "IC1") (pin "COMP") (pinfunction "COMP_COMP") (pintype "bidirectional"))
    )
    (net (code "115") (name "Net-(C5-Pad2)") (class "Default")
      (node (ref "C5") (pin "2") (pinfunction "2_2") (pintype "passive"))
      (node (ref "R7") (pin "2") (pinfunction "2_2") (pintype "passive"))
    )
    (net (code "116") (name "Net-(C8-Pad1)") (class "Default")
      (node (ref "C8") (pin "1") (pinfunction "1_1") (pintype "passive"))
      (node (ref "IC1") (pin "BS") (pinfunction "BS_BS") (pintype "bidirectional"))
    )
    (net (code "117") (name "Net-(C8-Pad2)") (class "Default")
      (node (ref "C8") (pin "2") (pinfunction "2_2") (pintype "passive"))
      (node (ref "IC1") (pin "SW") (pinfunction "SW_SW") (pintype "bidirectional"))
      (node (ref "L1") (pin "1") (pinfunction "1_1") (pintype "passive"))
    )
    (net (code "118") (name "Net-(C9-Pad1)") (class "Default")
      (node (ref "C9") (pin "1") (pinfunction "1_1") (pintype "passive"))
      (node (ref "IC1") (pin "SS") (pinfunction "SS_SS") (pintype "bidirectional"))
    )
    (net (code "119") (name "Net-(C12-Pad+)") (class "Default")
      (node (ref "C12") (pin "+") (pinfunction "+_+") (pintype "passive"))
      (node (ref "C7") (pin "1") (pinfunction "1_1") (pintype "passive"))
      (node (ref "L1") (pin "2") (pinfunction "2_2") (pintype "passive"))
      (node (ref "ON_BOARD_PWR") (pin "2") (pinfunction "2_2") (pintype "passive"))
      (node (ref "R12") (pin "1") (pinfunction "1_1") (pintype "passive"))
      (node (ref "R9") (pin "2") (pinfunction "2_2") (pintype "passive"))
    )
    (net (code "120") (name "Net-(C_STP-PadA)") (class "Default")
      (node (ref "C_STP") (pin "A") (pinfunction "A_A") (pintype "passive"))
      (node (ref "R3") (pin "1") (pinfunction "1_1") (pintype "passive"))
    )
    (net (code "121") (name "Net-(D2-PadA)") (class "Default")
      (node (ref "D2") (pin "A") (pinfunction "A_A") (pintype "passive"))
      (node (ref "ON_BOARD_PWR") (pin "1") (pinfunction "1_1") (pintype "passive"))
    )
    (net (code "122") (name "Net-(D13-PadA)") (class "Default")
      (node (ref "D13") (pin "A") (pinfunction "A_A") (pintype "passive"))
      (node (ref "RN1") (pin "1") (pinfunction "1_1") (pintype "passive"))
    )
    (net (code "123") (name "Net-(IC1-PadEN)") (class "Default")
      (node (ref "IC1") (pin "EN") (pinfunction "EN_EN") (pintype "bidirectional"))
      (node (ref "R4") (pin "2") (pinfunction "2_2") (pintype "passive"))
    )
    (net (code "124") (name "Net-(IC1-PadFB)") (class "Default")
      (node (ref "IC1") (pin "FB") (pinfunction "FB_FB") (pintype "bidirectional"))
      (node (ref "R10") (pin "2") (pinfunction "2_2") (pintype "passive"))
      (node (ref "R9") (pin "1") (pinfunction "1_1") (pintype "passive"))
    )
    (net (code "125") (name "Net-(PWR1-PadA)") (class "Default")
      (node (ref "PWR1") (pin "A") (pinfunction "A_A") (pintype "passive"))
      (node (ref "R12") (pin "2") (pinfunction "2_2") (pintype "passive"))
    )
    (net (code "126") (name "Net-(R1-Pad1)") (class "Default")
      (node (ref "R1") (pin "1") (pinfunction "1_1") (pintype "passive"))
      (node (ref "SJ7") (pin "2") (pinfunction "2_2") (pintype "passive"))
      (node (ref "U$1") (pin "MS1") (pinfunction "MS1_MS1") (pintype "input"))
    )
    (net (code "127") (name "Net-(R5-Pad1)") (class "Default")
      (node (ref "R5") (pin "1") (pinfunction "1_1") (pintype "passive"))
      (node (ref "SJ1") (pin "2") (pinfunction "2_2") (pintype "passive"))
      (node (ref "U$6") (pin "MS1") (pinfunction "MS1_MS1") (pintype "input"))
    )
    (net (code "128") (name "Net-(R8-Pad1)") (class "Default")
      (node (ref "R8") (pin "1") (pinfunction "1_1") (pintype "passive"))
      (node (ref "SJ3") (pin "2") (pinfunction "2_2") (pintype "passive"))
      (node (ref "U$7") (pin "MS1") (pinfunction "MS1_MS1") (pintype "input"))
    )
    (net (code "129") (name "Net-(RN1B-1)") (class "Default")
      (node (ref "RN1") (pin "2") (pinfunction "1_2") (pintype "passive"))
      (node (ref "RX_LED") (pin "C") (pinfunction "C_C") (pintype "passive"))
    )
    (net (code "130") (name "Net-(RN1C-1)") (class "Default")
      (node (ref "RN1") (pin "3") (pinfunction "1_3") (pintype "passive"))
      (node (ref "TX_LED") (pin "C") (pinfunction "C_C") (pintype "passive"))
    )
    (net (code "131") (name "Net-(RN1D-1)") (class "Default")
      (node (ref "PWR") (pin "A") (pinfunction "A_A") (pintype "passive"))
      (node (ref "RN1") (pin "4") (pinfunction "1_4") (pintype "passive"))
    )
    (net (code "132") (name "Net-(SJ2-Pad2)") (class "Default")
      (node (ref "SJ2") (pin "2") (pinfunction "2_2") (pintype "passive"))
      (node (ref "U$6") (pin "MS2") (pinfunction "MS2_MS2") (pintype "input"))
    )
    (net (code "133") (name "Net-(SJ4-Pad2)") (class "Default")
      (node (ref "SJ4") (pin "2") (pinfunction "2_2") (pintype "passive"))
      (node (ref "U$7") (pin "MS2") (pinfunction "MS2_MS2") (pintype "input"))
    )
    (net (code "134") (name "Net-(SJ5-Pad2)") (class "Default")
      (node (ref "SJ5") (pin "2") (pinfunction "2_2") (pintype "passive"))
      (node (ref "U$6") (pin "MS3") (pinfunction "MS3_MS3") (pintype "input"))
    )
    (net (code "135") (name "Net-(SJ6-Pad2)") (class "Default")
      (node (ref "SJ6") (pin "2") (pinfunction "2_2") (pintype "passive"))
      (node (ref "U$7") (pin "MS3") (pinfunction "MS3_MS3") (pintype "input"))
    )
    (net (code "136") (name "Net-(SJ8-Pad2)") (class "Default")
      (node (ref "SJ8") (pin "2") (pinfunction "2_2") (pintype "passive"))
      (node (ref "U$1") (pin "MS2") (pinfunction "MS2_MS2") (pintype "input"))
    )
    (net (code "137") (name "Net-(SJ9-Pad2)") (class "Default")
      (node (ref "SJ9") (pin "2") (pinfunction "2_2") (pintype "passive"))
      (node (ref "U$1") (pin "MS3") (pinfunction "MS3_MS3") (pintype "input"))
    )
    (net (code "138") (name "Net-(U$1-SLEEP)") (class "Default")
      (node (ref "U$1") (pin "RST") (pinfunction "RST_RST") (pintype "input"))
      (node (ref "U$1") (pin "SLP") (pinfunction "SLEEP_SLP") (pintype "input"))
    )
    (net (code "139") (name "Net-(U$6-SLEEP)") (class "Default")
      (node (ref "U$6") (pin "RST") (pinfunction "RST_RST") (pintype "input"))
      (node (ref "U$6") (pin "SLP") (pinfunction "SLEEP_SLP") (pintype "input"))
    )
    (net (code "140") (name "Net-(U$7-SLEEP)") (class "Default")
      (node (ref "U$7") (pin "RST") (pinfunction "RST_RST") (pintype "input"))
      (node (ref "U$7") (pin "SLP") (pinfunction "SLEEP_SLP") (pintype "input"))
    )
    (net (code "141") (name "VCC") (class "Default")
      (node (ref "D2") (pin "C") (pinfunction "C_C") (pintype "passive"))
      (node (ref "IC5") (pin "20") (pinfunction "VCC_20") (pintype "power_in"))
      (node (ref "R18") (pin "1") (pinfunction "1_1") (pintype "passive"))
      (node (ref "R19") (pin "1") (pinfunction "1_1") (pintype "passive"))
      (node (ref "R2") (pin "1") (pinfunction "1_1") (pintype "passive"))
      (node (ref "RN1") (pin "5") (pinfunction "2_5") (pintype "passive"))
      (node (ref "RX_LED") (pin "A") (pinfunction "A_A") (pintype "passive"))
      (node (ref "SER1") (pin "2") (pinfunction "2_2") (pintype "passive"))
      (node (ref "SER2") (pin "2") (pinfunction "2_2") (pintype "passive"))
      (node (ref "SJ1") (pin "1") (pinfunction "1_1") (pintype "passive"))
      (node (ref "SJ2") (pin "1") (pinfunction "1_1") (pintype "passive"))
      (node (ref "SJ3") (pin "1") (pinfunction "1_1") (pintype "passive"))
      (node (ref "SJ4") (pin "1") (pinfunction "1_1") (pintype "passive"))
      (node (ref "SJ5") (pin "1") (pinfunction "1_1") (pintype "passive"))
      (node (ref "SJ6") (pin "1") (pinfunction "1_1") (pintype "passive"))
      (node (ref "SJ7") (pin "1") (pinfunction "1_1") (pintype "passive"))
      (node (ref "SJ8") (pin "1") (pinfunction "1_1") (pintype "passive"))
      (node (ref "SJ9") (pin "1") (pinfunction "1_1") (pintype "passive"))
      (node (ref "TFT") (pin "3") (pinfunction "3_3") (pintype "passive"))
      (node (ref "TX_LED") (pin "A") (pinfunction "A_A") (pintype "passive"))
      (node (ref "U$1") (pin "VDD") (pinfunction "VDD_VDD") (pintype "power_in"))
      (node (ref "U$6") (pin "VDD") (pinfunction "VDD_VDD") (pintype "power_in"))
      (node (ref "U$7") (pin "VDD") (pinfunction "VDD_VDD") (pintype "power_in"))
      (node (ref "U1") (pin "5V@0") (pinfunction "5V_5V@0") (pintype "power_in"))
      (node (ref "U1") (pin "5V@1") (pinfunction "5V_5V@1") (pintype "power_in"))
      (node (ref "U1") (pin "5V@2") (pinfunction "5V_5V@2") (pintype "power_in"))
      (node (ref "X-MAX") (pin "2") (pinfunction "2_2") (pintype "passive"))
      (node (ref "X-MIN") (pin "2") (pinfunction "2_2") (pintype "passive"))
      (node (ref "Y-MAX") (pin "2") (pinfunction "2_2") (pintype "passive"))
      (node (ref "Y-MIN") (pin "2") (pinfunction "2_2") (pintype "passive"))
    )
    (net (code "142") (name "unconnected-(IC3A-Y3-Pad16)") (class "Default")
      (node (ref "IC3") (pin "16") (pinfunction "Y3_16") (pintype "tri_state"))
    )
    (net (code "143") (name "unconnected-(IC3A-Y4-Pad15)") (class "Default")
      (node (ref "IC3") (pin "15") (pinfunction "Y4_15") (pintype "tri_state"))
    )
    (net (code "144") (name "unconnected-(IC3A-Y5-Pad14)") (class "Default")
      (node (ref "IC3") (pin "14") (pinfunction "Y5_14") (pintype "tri_state"))
    )
    (net (code "145") (name "unconnected-(IC3A-Y6-Pad13)") (class "Default")
      (node (ref "IC3") (pin "13") (pinfunction "Y6_13") (pintype "tri_state"))
    )
    (net (code "146") (name "unconnected-(IC3A-Y8-Pad11)") (class "Default")
      (node (ref "IC3") (pin "11") (pinfunction "Y8_11") (pintype "tri_state"))
    )
    (net (code "147") (name "unconnected-(IC4A-Y8-Pad11)") (class "Default")
      (node (ref "IC4") (pin "11") (pinfunction "Y8_11") (pintype "tri_state"))
    )
    (net (code "148") (name "unconnected-(IC5A-Y1-Pad18)") (class "Default")
      (node (ref "IC5") (pin "18") (pinfunction "Y1_18") (pintype "tri_state"))
    )
    (net (code "149") (name "unconnected-(IC5A-Y5-Pad14)") (class "Default")
      (node (ref "IC5") (pin "14") (pinfunction "Y5_14") (pintype "tri_state"))
    )
    (net (code "150") (name "unconnected-(IC5A-Y6-Pad13)") (class "Default")
      (node (ref "IC5") (pin "13") (pinfunction "Y6_13") (pintype "tri_state"))
    )
    (net (code "151") (name "unconnected-(IC5A-Y7-Pad12)") (class "Default")
      (node (ref "IC5") (pin "12") (pinfunction "Y7_12") (pintype "tri_state"))
    )
    (net (code "152") (name "unconnected-(IC5A-Y8-Pad11)") (class "Default")
      (node (ref "IC5") (pin "11") (pinfunction "Y8_11") (pintype "tri_state"))
    )
    (net (code "153") (name "unconnected-(TFT-Pad5)") (class "Default")
      (node (ref "TFT") (pin "5") (pinfunction "5_5") (pintype "passive"))
    )
    (net (code "154") (name "unconnected-(TFT-Pad24)") (class "Default")
      (node (ref "TFT") (pin "24") (pinfunction "24_24") (pintype "passive"))
    )
    (net (code "155") (name "unconnected-(TFT-Pad31)") (class "Default")
      (node (ref "TFT") (pin "31") (pinfunction "31_31") (pintype "passive"))
    )
    (net (code "156") (name "unconnected-(TFT-Pad35)") (class "Default")
      (node (ref "TFT") (pin "35") (pinfunction "35_35") (pintype "passive"))
    )
    (net (code "157") (name "unconnected-(TFT-Pad38)") (class "Default")
      (node (ref "TFT") (pin "38") (pinfunction "38_38") (pintype "passive"))
    )
    (net (code "158") (name "unconnected-(TFT-Pad39)") (class "Default")
      (node (ref "TFT") (pin "39") (pinfunction "39_39") (pintype "passive"))
    )
    (net (code "159") (name "unconnected-(TFT-Pad40)") (class "Default")
      (node (ref "TFT") (pin "40") (pinfunction "40_40") (pintype "passive"))
    )
  )
)
